# sch_CPU.net
KiCad netlist of a schematic drawn in Altium Designer
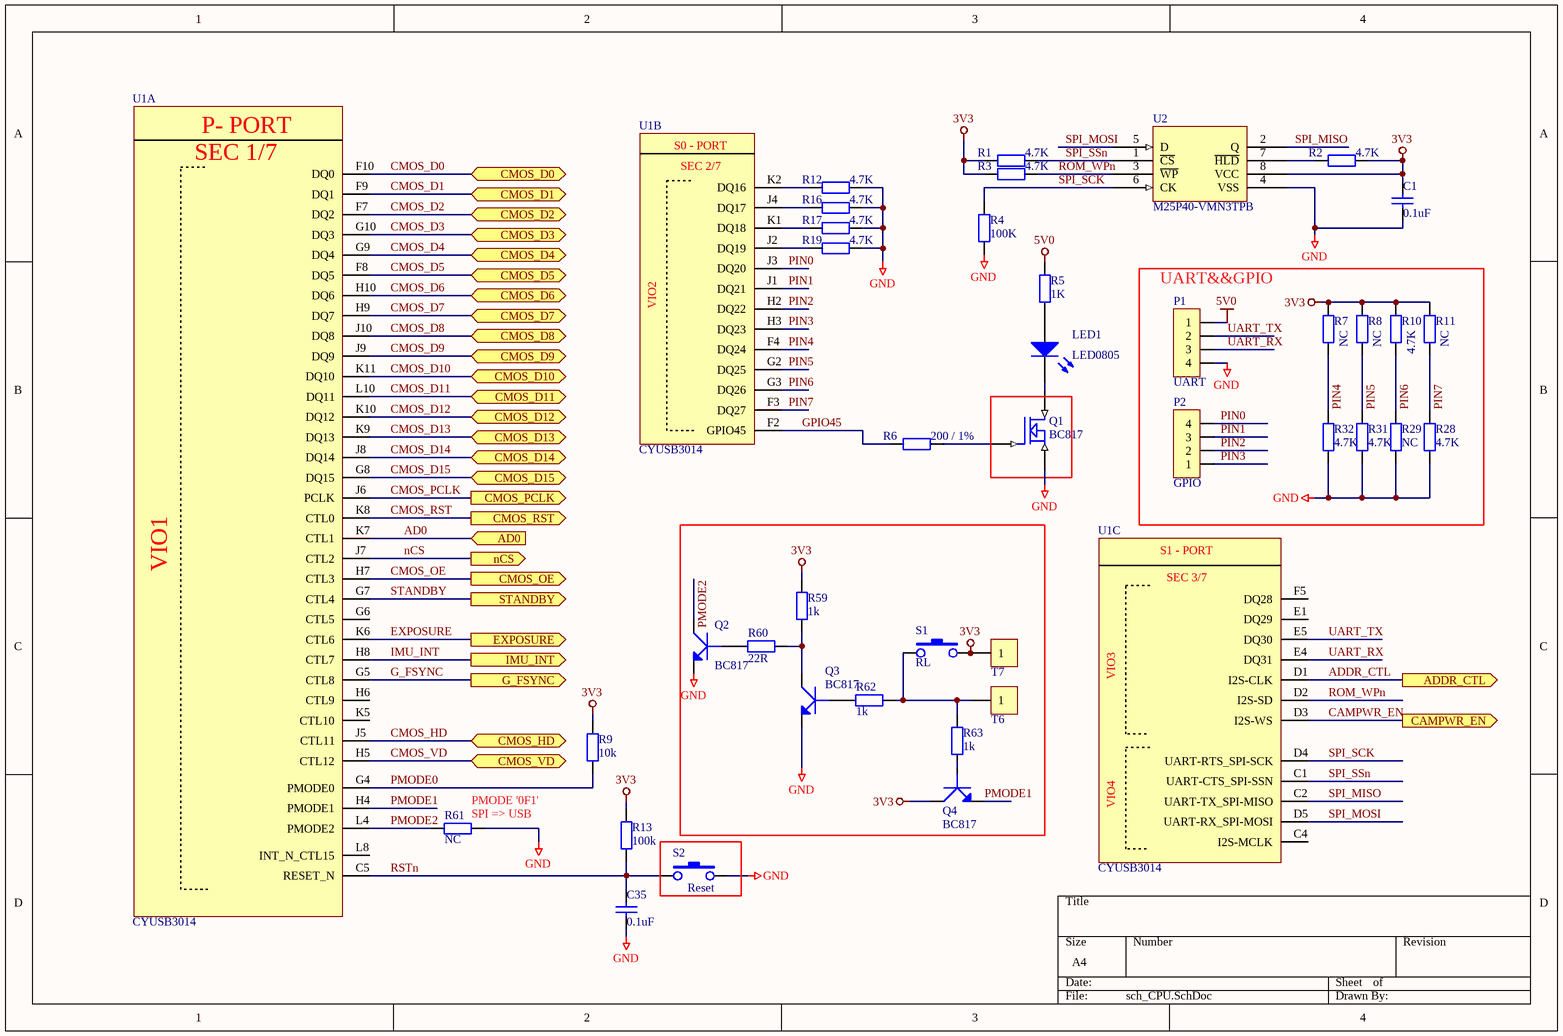
[diagram p0: sch_CPU.SchDoc]

(export (version "E")
  (design (tool "Eeschema 10.0.6"))
  (components
    (comp (ref "C1")
      (value "0.1uF")
      (footprint "0402C")
      (description "Capacitor")
      (fields (field (name "PUBLISHER") "Altium Limited"))
      (libsource (lib "Miscellaneous Devices") (part "Cap"))
    )
    (comp (ref "C35")
      (value "0.1uF")
      (footprint "0402C")
      (description "Capacitor")
      (fields (field (name "PUBLISHER") "Altium Limited"))
      (libsource (lib "Miscellaneous Devices") (part "Cap"))
    )
    (comp (ref "LED1")
      (value "LED0805")
      (footprint "LED0805A_L210W100H60")
      (description "发光二级管")
      (libsource (lib "TXW") (part "LED"))
    )
    (comp (ref "P1")
      (value "UART")
      (footprint "WAFER4_P1.25L6.25W3.4H4.3")
      (libsource (lib "KS_Drive") (part "CON4"))
    )
    (comp (ref "P2")
      (value "GPIO")
      (footprint "WAFER4_P1.25L6.25W3.4H4.3")
      (libsource (lib "") (part "CON4_1"))
    )
    (comp (ref "Q1")
      (value "BC817")
      (footprint "SOT-23L")
      (description "MOSFET N")
      (libsource (lib "TXW") (part "MOSFET N"))
    )
    (comp (ref "Q2")
      (value "BC817")
      (footprint "SOT-23L")
      (description "NPN Transistor")
      (libsource (lib "*") (part "NPN"))
    )
    (comp (ref "Q3")
      (value "BC817")
      (footprint "SOT-23L")
      (description "NPN Transistor")
      (libsource (lib "*") (part "NPN"))
    )
    (comp (ref "Q4")
      (value "BC817")
      (footprint "SOT-23L")
      (description "NPN Transistor")
      (libsource (lib "") (part "NPN_1"))
    )
    (comp (ref "R1")
      (value "4.7K")
      (footprint "0402R")
      (description "Resistor")
      (fields (field (name "PUBLISHER") "Altium Limited"))
      (libsource (lib "SZG") (part "Resistor"))
    )
    (comp (ref "R2")
      (value "4.7K")
      (footprint "0402R")
      (description "Resistor")
      (fields (field (name "PUBLISHER") "Altium Limited"))
      (libsource (lib "SZG") (part "Resistor"))
    )
    (comp (ref "R3")
      (value "4.7K")
      (footprint "0402R")
      (description "Resistor")
      (fields (field (name "PUBLISHER") "Altium Limited"))
      (libsource (lib "SZG") (part "Resistor"))
    )
    (comp (ref "R4")
      (value "100K")
      (footprint "0402R")
      (description "Resistor")
      (fields (field (name "PUBLISHER") "Altium Limited"))
      (libsource (lib "") (part "Resistor_1"))
    )
    (comp (ref "R5")
      (value "1K")
      (footprint "0402R")
      (description "Resistor")
      (fields (field (name "PUBLISHER") "Altium Limited"))
      (libsource (lib "") (part "Resistor_2"))
    )
    (comp (ref "R6")
      (value "200 / 1%")
      (footprint "0402R")
      (description "Resistor")
      (fields (field (name "Comment") "200R") (field (name "PUBLISHER") "Altium Limited"))
      (libsource (lib "SZG") (part "Resistor"))
    )
    (comp (ref "R7")
      (value "NC")
      (footprint "0402R")
      (description "Resistor")
      (fields (field (name "PUBLISHER") "Altium Limited"))
      (libsource (lib "") (part "Resistor_1"))
    )
    (comp (ref "R8")
      (value "NC")
      (footprint "0402R")
      (description "Resistor")
      (fields (field (name "PUBLISHER") "Altium Limited"))
      (libsource (lib "") (part "Resistor_1"))
    )
    (comp (ref "R9")
      (value "10k")
      (footprint "0402R")
      (description "Resistor")
      (fields (field (name "Comment") "10K") (field (name "PUBLISHER") "Altium Limited"))
      (libsource (lib "") (part "Resistor_2"))
    )
    (comp (ref "R10")
      (value "4.7K")
      (footprint "0402R")
      (description "Resistor")
      (fields (field (name "PUBLISHER") "Altium Limited"))
      (libsource (lib "") (part "Resistor_1"))
    )
    (comp (ref "R11")
      (value "NC")
      (footprint "0402R")
      (description "Resistor")
      (fields (field (name "PUBLISHER") "Altium Limited"))
      (libsource (lib "") (part "Resistor_1"))
    )
    (comp (ref "R12")
      (value "4.7K")
      (footprint "0402R")
      (description "Resistor")
      (fields (field (name "PUBLISHER") "Altium Limited"))
      (libsource (lib "SZG") (part "Resistor"))
    )
    (comp (ref "R13")
      (value "100k")
      (footprint "0402R")
      (description "Resistor")
      (fields (field (name "Comment") "100K") (field (name "PUBLISHER") "Altium Limited"))
      (libsource (lib "") (part "Resistor_2"))
    )
    (comp (ref "R16")
      (value "4.7K")
      (footprint "0402R")
      (description "Resistor")
      (fields (field (name "PUBLISHER") "Altium Limited"))
      (libsource (lib "SZG") (part "Resistor"))
    )
    (comp (ref "R17")
      (value "4.7K")
      (footprint "0402R")
      (description "Resistor")
      (fields (field (name "PUBLISHER") "Altium Limited"))
      (libsource (lib "SZG") (part "Resistor"))
    )
    (comp (ref "R19")
      (value "4.7K")
      (footprint "0402R")
      (description "Resistor")
      (fields (field (name "PUBLISHER") "Altium Limited"))
      (libsource (lib "SZG") (part "Resistor"))
    )
    (comp (ref "R28")
      (value "4.7K")
      (footprint "0402R")
      (description "Resistor")
      (fields (field (name "PUBLISHER") "Altium Limited"))
      (libsource (lib "") (part "Resistor_2"))
    )
    (comp (ref "R29")
      (value "NC")
      (footprint "0402R")
      (description "Resistor")
      (fields (field (name "PUBLISHER") "Altium Limited"))
      (libsource (lib "") (part "Resistor_2"))
    )
    (comp (ref "R31")
      (value "4.7K")
      (footprint "0402R")
      (description "Resistor")
      (fields (field (name "PUBLISHER") "Altium Limited"))
      (libsource (lib "") (part "Resistor_2"))
    )
    (comp (ref "R32")
      (value "4.7K")
      (footprint "0402R")
      (description "Resistor")
      (fields (field (name "PUBLISHER") "Altium Limited"))
      (libsource (lib "") (part "Resistor_2"))
    )
    (comp (ref "R59")
      (value "1k")
      (footprint "0402R")
      (description "Resistor")
      (fields (field (name "Comment") "1K") (field (name "PUBLISHER") "Altium Limited"))
      (libsource (lib "") (part "Resistor_1"))
    )
    (comp (ref "R60")
      (value "22R")
      (footprint "0402R")
      (description "Resistor")
      (fields (field (name "PUBLISHER") "Altium Limited"))
      (libsource (lib "SZG") (part "Resistor"))
    )
    (comp (ref "R61")
      (value "NC")
      (footprint "0805R")
      (description "Resistor")
      (fields (field (name "PUBLISHER") "Altium Limited"))
      (libsource (lib "") (part "Resistor_3"))
    )
    (comp (ref "R62")
      (value "1k")
      (footprint "0402R")
      (description "Resistor")
      (fields (field (name "PUBLISHER") "Altium Limited"))
      (libsource (lib "") (part "Resistor_3"))
    )
    (comp (ref "R63")
      (value "1k")
      (footprint "0402R")
      (description "Resistor")
      (fields (field (name "PUBLISHER") "Altium Limited"))
      (libsource (lib "") (part "Resistor_2"))
    )
    (comp (ref "S1")
      (value "RL")
      (footprint "SW_L40W30H25_MPTFP")
      (description "Button_sop")
      (libsource (lib "SZG") (part "Button_sop"))
    )
    (comp (ref "S2")
      (value "Reset")
      (footprint "SW_L40W30H25_MPTFP")
      (description "Button_sop")
      (libsource (lib "SZG") (part "Button_sop"))
    )
    (comp (ref "T6")
      (value "CON1")
      (footprint "PAD_TP_D1.2")
      (description "Connector")
      (libsource (lib "SuperSchLib") (part "CON1"))
    )
    (comp (ref "T7")
      (value "CON1")
      (footprint "PAD_TP_D1.2")
      (description "Connector")
      (libsource (lib "SuperSchLib") (part "CON1"))
    )
    (comp (ref "U1")
      (value "CYUSB3014")
      (footprint "FBGA121_P80L100W100H11")
      (libsource (lib "TXW") (part "CYUSB3014"))
    )
    (comp (ref "U2")
      (value "M25P40-VMN3TPB")
      (footprint "SO8N_P127L50W40W62H17")
      (libsource (lib "TXW") (part "M25P40-VMN3TPB"))
    )
  )
  (nets
    (net (code "1") (name "/AD0") (class "Default")
      (node (ref "U1") (pin "K7") (pinfunction "CTL1_K7") (pintype "passive"))
    )
    (net (code "2") (name "/ADDR_CTL") (class "Default")
      (node (ref "U1") (pin "D1") (pinfunction "I2S-CLK_D1") (pintype "passive"))
    )
    (net (code "3") (name "/CAMPWR_EN") (class "Default")
      (node (ref "U1") (pin "D3") (pinfunction "I2S-WS_D3") (pintype "passive"))
    )
    (net (code "4") (name "/CMOS_D0") (class "Default")
      (node (ref "U1") (pin "F10") (pinfunction "DQ0_F10") (pintype "passive"))
    )
    (net (code "5") (name "/CMOS_D1") (class "Default")
      (node (ref "U1") (pin "F9") (pinfunction "DQ1_F9") (pintype "passive"))
    )
    (net (code "6") (name "/CMOS_D2") (class "Default")
      (node (ref "U1") (pin "F7") (pinfunction "DQ2_F7") (pintype "passive"))
    )
    (net (code "7") (name "/CMOS_D3") (class "Default")
      (node (ref "U1") (pin "G10") (pinfunction "DQ3_G10") (pintype "passive"))
    )
    (net (code "8") (name "/CMOS_D4") (class "Default")
      (node (ref "U1") (pin "G9") (pinfunction "DQ4_G9") (pintype "passive"))
    )
    (net (code "9") (name "/CMOS_D5") (class "Default")
      (node (ref "U1") (pin "F8") (pinfunction "DQ5_F8") (pintype "passive"))
    )
    (net (code "10") (name "/CMOS_D6") (class "Default")
      (node (ref "U1") (pin "H10") (pinfunction "DQ6_H10") (pintype "passive"))
    )
    (net (code "11") (name "/CMOS_D7") (class "Default")
      (node (ref "U1") (pin "H9") (pinfunction "DQ7_H9") (pintype "passive"))
    )
    (net (code "12") (name "/CMOS_D8") (class "Default")
      (node (ref "U1") (pin "J10") (pinfunction "DQ8_J10") (pintype "passive"))
    )
    (net (code "13") (name "/CMOS_D9") (class "Default")
      (node (ref "U1") (pin "J9") (pinfunction "DQ9_J9") (pintype "passive"))
    )
    (net (code "14") (name "/CMOS_D10") (class "Default")
      (node (ref "U1") (pin "K11") (pinfunction "DQ10_K11") (pintype "passive"))
    )
    (net (code "15") (name "/CMOS_D11") (class "Default")
      (node (ref "U1") (pin "L10") (pinfunction "DQ11_L10") (pintype "passive"))
    )
    (net (code "16") (name "/CMOS_D12") (class "Default")
      (node (ref "U1") (pin "K10") (pinfunction "DQ12_K10") (pintype "passive"))
    )
    (net (code "17") (name "/CMOS_D13") (class "Default")
      (node (ref "U1") (pin "K9") (pinfunction "DQ13_K9") (pintype "passive"))
    )
    (net (code "18") (name "/CMOS_D14") (class "Default")
      (node (ref "U1") (pin "J8") (pinfunction "DQ14_J8") (pintype "passive"))
    )
    (net (code "19") (name "/CMOS_D15") (class "Default")
      (node (ref "U1") (pin "G8") (pinfunction "DQ15_G8") (pintype "passive"))
    )
    (net (code "20") (name "/CMOS_HD") (class "Default")
      (node (ref "U1") (pin "J5") (pinfunction "CTL11_J5") (pintype "passive"))
    )
    (net (code "21") (name "/CMOS_OE") (class "Default")
      (node (ref "U1") (pin "H7") (pinfunction "CTL3_H7") (pintype "passive"))
    )
    (net (code "22") (name "/CMOS_PCLK") (class "Default")
      (node (ref "U1") (pin "J6") (pinfunction "PCLK_J6") (pintype "passive"))
    )
    (net (code "23") (name "/CMOS_RST") (class "Default")
      (node (ref "U1") (pin "K8") (pinfunction "CTL0_K8") (pintype "passive"))
    )
    (net (code "24") (name "/CMOS_VD") (class "Default")
      (node (ref "U1") (pin "H5") (pinfunction "CTL12_H5") (pintype "passive"))
    )
    (net (code "25") (name "/EXPOSURE") (class "Default")
      (node (ref "U1") (pin "K6") (pinfunction "CTL6_K6") (pintype "passive"))
    )
    (net (code "26") (name "/GPIO45") (class "Default")
      (node (ref "R6") (pin "1") (pinfunction "1_1") (pintype "passive"))
      (node (ref "U1") (pin "F2") (pinfunction "GPIO45_F2") (pintype "passive"))
    )
    (net (code "27") (name "/G_FSYNC") (class "Default")
      (node (ref "U1") (pin "G5") (pinfunction "CTL8_G5") (pintype "passive"))
    )
    (net (code "28") (name "/IMU_INT") (class "Default")
      (node (ref "U1") (pin "H8") (pinfunction "CTL7_H8") (pintype "passive"))
    )
    (net (code "29") (name "/PIN0") (class "Default")
      (node (ref "P2") (pin "4") (pinfunction "4_4") (pintype "passive"))
      (node (ref "U1") (pin "J3") (pinfunction "DQ20_J3") (pintype "passive"))
    )
    (net (code "30") (name "/PIN1") (class "Default")
      (node (ref "P2") (pin "3") (pinfunction "3_3") (pintype "passive"))
      (node (ref "U1") (pin "J1") (pinfunction "DQ21_J1") (pintype "passive"))
    )
    (net (code "31") (name "/PIN2") (class "Default")
      (node (ref "P2") (pin "2") (pinfunction "2_2") (pintype "passive"))
      (node (ref "U1") (pin "H2") (pinfunction "DQ22_H2") (pintype "passive"))
    )
    (net (code "32") (name "/PIN3") (class "Default")
      (node (ref "P2") (pin "1") (pinfunction "1_1") (pintype "passive"))
      (node (ref "U1") (pin "H3") (pinfunction "DQ23_H3") (pintype "passive"))
    )
    (net (code "33") (name "/PIN4") (class "Default")
      (node (ref "R32") (pin "1") (pinfunction "1_1") (pintype "passive"))
      (node (ref "R7") (pin "1") (pinfunction "1_1") (pintype "passive"))
      (node (ref "U1") (pin "F4") (pinfunction "DQ24_F4") (pintype "passive"))
    )
    (net (code "34") (name "/PIN5") (class "Default")
      (node (ref "R31") (pin "1") (pinfunction "1_1") (pintype "passive"))
      (node (ref "R8") (pin "1") (pinfunction "1_1") (pintype "passive"))
      (node (ref "U1") (pin "G2") (pinfunction "DQ25_G2") (pintype "passive"))
    )
    (net (code "35") (name "/PIN6") (class "Default")
      (node (ref "R10") (pin "1") (pinfunction "1_1") (pintype "passive"))
      (node (ref "R29") (pin "1") (pinfunction "1_1") (pintype "passive"))
      (node (ref "U1") (pin "G3") (pinfunction "DQ26_G3") (pintype "passive"))
    )
    (net (code "36") (name "/PIN7") (class "Default")
      (node (ref "R11") (pin "1") (pinfunction "1_1") (pintype "passive"))
      (node (ref "R28") (pin "1") (pinfunction "1_1") (pintype "passive"))
      (node (ref "U1") (pin "F3") (pinfunction "DQ27_F3") (pintype "passive"))
    )
    (net (code "37") (name "/PMODE0") (class "Default")
      (node (ref "R9") (pin "2") (pinfunction "2_2") (pintype "passive"))
      (node (ref "U1") (pin "G4") (pinfunction "PMODE0_G4") (pintype "passive"))
    )
    (net (code "38") (name "/PMODE1") (class "Default")
      (node (ref "Q4") (pin "2") (pinfunction "E_2") (pintype "passive"))
      (node (ref "U1") (pin "H4") (pinfunction "PMODE1_H4") (pintype "passive"))
    )
    (net (code "39") (name "/PMODE2") (class "Default")
      (node (ref "Q2") (pin "3") (pinfunction "C_3") (pintype "passive"))
      (node (ref "R61") (pin "2") (pinfunction "2_2") (pintype "passive"))
      (node (ref "U1") (pin "L4") (pinfunction "PMODE2_L4") (pintype "passive"))
    )
    (net (code "40") (name "/ROM_WPn") (class "Default")
      (node (ref "R3") (pin "2") (pinfunction "2_2") (pintype "passive"))
      (node (ref "U1") (pin "D2") (pinfunction "I2S-SD_D2") (pintype "passive"))
      (node (ref "U2") (pin "3") (pinfunction "~{WP}_3") (pintype "passive"))
    )
    (net (code "41") (name "/RSTn") (class "Default")
      (node (ref "C35") (pin "2") (pinfunction "2_2") (pintype "passive"))
      (node (ref "R13") (pin "2") (pinfunction "2_2") (pintype "passive"))
      (node (ref "S2") (pin "1") (pinfunction "1_1") (pintype "passive"))
      (node (ref "U1") (pin "C5") (pinfunction "RESET_N_C5") (pintype "passive"))
    )
    (net (code "42") (name "/SPI_MISO") (class "Default")
      (node (ref "U1") (pin "C2") (pinfunction "UART-TX_SPI-MISO_C2") (pintype "passive"))
      (node (ref "U2") (pin "2") (pinfunction "Q_2") (pintype "passive"))
    )
    (net (code "43") (name "/SPI_MOSI") (class "Default")
      (node (ref "U1") (pin "D5") (pinfunction "UART-RX_SPI-MOSI_D5") (pintype "passive"))
      (node (ref "U2") (pin "5") (pinfunction "D_5") (pintype "input"))
    )
    (net (code "44") (name "/SPI_SCK") (class "Default")
      (node (ref "R4") (pin "2") (pinfunction "2_2") (pintype "passive"))
      (node (ref "U1") (pin "D4") (pinfunction "UART-RTS_SPI-SCK_D4") (pintype "passive"))
      (node (ref "U2") (pin "6") (pinfunction "CK_6") (pintype "input"))
    )
    (net (code "45") (name "/SPI_SSn") (class "Default")
      (node (ref "R1") (pin "2") (pinfunction "2_2") (pintype "passive"))
      (node (ref "U1") (pin "C1") (pinfunction "UART-CTS_SPI-SSN_C1") (pintype "passive"))
      (node (ref "U2") (pin "1") (pinfunction "~{CS}_1") (pintype "passive"))
    )
    (net (code "46") (name "/STANDBY") (class "Default")
      (node (ref "U1") (pin "G7") (pinfunction "CTL4_G7") (pintype "passive"))
    )
    (net (code "47") (name "/UART_RX") (class "Default")
      (node (ref "P1") (pin "3") (pinfunction "3_3") (pintype "passive"))
      (node (ref "U1") (pin "E4") (pinfunction "DQ31_E4") (pintype "passive"))
    )
    (net (code "48") (name "/UART_TX") (class "Default")
      (node (ref "P1") (pin "2") (pinfunction "2_2") (pintype "passive"))
      (node (ref "U1") (pin "E5") (pinfunction "DQ30_E5") (pintype "passive"))
    )
    (net (code "49") (name "/nCS") (class "Default")
      (node (ref "U1") (pin "J7") (pinfunction "CTL2_J7") (pintype "passive"))
    )
    (net (code "50") (name "3V3") (class "Default")
      (node (ref "C1") (pin "2") (pinfunction "2_2") (pintype "passive"))
      (node (ref "Q4") (pin "3") (pinfunction "C_3") (pintype "passive"))
      (node (ref "R1") (pin "1") (pinfunction "1_1") (pintype "passive"))
      (node (ref "R10") (pin "2") (pinfunction "2_2") (pintype "passive"))
      (node (ref "R11") (pin "2") (pinfunction "2_2") (pintype "passive"))
      (node (ref "R13") (pin "1") (pinfunction "1_1") (pintype "passive"))
      (node (ref "R2") (pin "2") (pinfunction "2_2") (pintype "passive"))
      (node (ref "R3") (pin "1") (pinfunction "1_1") (pintype "passive"))
      (node (ref "R59") (pin "2") (pinfunction "2_2") (pintype "passive"))
      (node (ref "R7") (pin "2") (pinfunction "2_2") (pintype "passive"))
      (node (ref "R8") (pin "2") (pinfunction "2_2") (pintype "passive"))
      (node (ref "R9") (pin "1") (pinfunction "1_1") (pintype "passive"))
      (node (ref "S1") (pin "1") (pinfunction "1_1") (pintype "passive"))
      (node (ref "T7") (pin "1") (pinfunction "1_1") (pintype "passive"))
      (node (ref "U2") (pin "8") (pinfunction "VCC_8") (pintype "passive"))
    )
    (net (code "51") (name "5V0") (class "Default")
      (node (ref "P1") (pin "1") (pinfunction "1_1") (pintype "passive"))
      (node (ref "R5") (pin "1") (pinfunction "1_1") (pintype "passive"))
    )
    (net (code "52") (name "GND") (class "Default")
      (node (ref "C1") (pin "1") (pinfunction "1_1") (pintype "passive"))
      (node (ref "C35") (pin "1") (pinfunction "1_1") (pintype "passive"))
      (node (ref "P1") (pin "4") (pinfunction "4_4") (pintype "passive"))
      (node (ref "Q1") (pin "2") (pinfunction "S_2") (pintype "input"))
      (node (ref "Q2") (pin "2") (pinfunction "E_2") (pintype "passive"))
      (node (ref "Q3") (pin "2") (pinfunction "E_2") (pintype "passive"))
      (node (ref "R12") (pin "2") (pinfunction "2_2") (pintype "passive"))
      (node (ref "R16") (pin "2") (pinfunction "2_2") (pintype "passive"))
      (node (ref "R17") (pin "2") (pinfunction "2_2") (pintype "passive"))
      (node (ref "R19") (pin "2") (pinfunction "2_2") (pintype "passive"))
      (node (ref "R28") (pin "2") (pinfunction "2_2") (pintype "passive"))
      (node (ref "R29") (pin "2") (pinfunction "2_2") (pintype "passive"))
      (node (ref "R31") (pin "2") (pinfunction "2_2") (pintype "passive"))
      (node (ref "R32") (pin "2") (pinfunction "2_2") (pintype "passive"))
      (node (ref "R4") (pin "1") (pinfunction "1_1") (pintype "passive"))
      (node (ref "R61") (pin "1") (pinfunction "1_1") (pintype "passive"))
      (node (ref "S2") (pin "2") (pinfunction "2_2") (pintype "passive"))
      (node (ref "U2") (pin "4") (pinfunction "VSS_4") (pintype "passive"))
    )
    (net (code "53") (name "Net-(LED1-A)") (class "Default")
      (node (ref "LED1") (pin "1") (pinfunction "A_1") (pintype "passive"))
      (node (ref "R5") (pin "2") (pinfunction "2_2") (pintype "passive"))
    )
    (net (code "54") (name "Net-(LED1-K)") (class "Default")
      (node (ref "LED1") (pin "2") (pinfunction "K_2") (pintype "passive"))
      (node (ref "Q1") (pin "3") (pinfunction "D_3") (pintype "input"))
    )
    (net (code "55") (name "Net-(Q1-G)") (class "Default")
      (node (ref "Q1") (pin "1") (pinfunction "G_1") (pintype "input"))
      (node (ref "R6") (pin "2") (pinfunction "2_2") (pintype "passive"))
    )
    (net (code "56") (name "Net-(Q2-B)") (class "Default")
      (node (ref "Q2") (pin "1") (pinfunction "B_1") (pintype "passive"))
      (node (ref "R60") (pin "1") (pinfunction "1_1") (pintype "passive"))
    )
    (net (code "57") (name "Net-(Q3-B)") (class "Default")
      (node (ref "Q3") (pin "1") (pinfunction "B_1") (pintype "passive"))
      (node (ref "R62") (pin "2") (pinfunction "2_2") (pintype "passive"))
    )
    (net (code "58") (name "Net-(Q3-C)") (class "Default")
      (node (ref "Q3") (pin "3") (pinfunction "C_3") (pintype "passive"))
      (node (ref "R59") (pin "1") (pinfunction "1_1") (pintype "passive"))
      (node (ref "R60") (pin "2") (pinfunction "2_2") (pintype "passive"))
    )
    (net (code "59") (name "Net-(Q4-B)") (class "Default")
      (node (ref "Q4") (pin "1") (pinfunction "B_1") (pintype "passive"))
      (node (ref "R63") (pin "2") (pinfunction "2_2") (pintype "passive"))
    )
    (net (code "60") (name "Net-(R62-Pad1)") (class "Default")
      (node (ref "R62") (pin "1") (pinfunction "1_1") (pintype "passive"))
      (node (ref "R63") (pin "1") (pinfunction "1_1") (pintype "passive"))
      (node (ref "S1") (pin "2") (pinfunction "2_2") (pintype "passive"))
      (node (ref "T6") (pin "1") (pinfunction "1_1") (pintype "passive"))
    )
    (net (code "61") (name "Net-(U1B-DQ16)") (class "Default")
      (node (ref "R12") (pin "1") (pinfunction "1_1") (pintype "passive"))
      (node (ref "U1") (pin "K2") (pinfunction "DQ16_K2") (pintype "passive"))
    )
    (net (code "62") (name "Net-(U1B-DQ17)") (class "Default")
      (node (ref "R16") (pin "1") (pinfunction "1_1") (pintype "passive"))
      (node (ref "U1") (pin "J4") (pinfunction "DQ17_J4") (pintype "passive"))
    )
    (net (code "63") (name "Net-(U1B-DQ18)") (class "Default")
      (node (ref "R17") (pin "1") (pinfunction "1_1") (pintype "passive"))
      (node (ref "U1") (pin "K1") (pinfunction "DQ18_K1") (pintype "passive"))
    )
    (net (code "64") (name "Net-(U1B-DQ19)") (class "Default")
      (node (ref "R19") (pin "1") (pinfunction "1_1") (pintype "passive"))
      (node (ref "U1") (pin "J2") (pinfunction "DQ19_J2") (pintype "passive"))
    )
    (net (code "65") (name "Net-(U2-~{HLD})") (class "Default")
      (node (ref "R2") (pin "1") (pinfunction "1_1") (pintype "passive"))
      (node (ref "U2") (pin "7") (pinfunction "~{HLD}_7") (pintype "passive"))
    )
    (net (code "66") (name "unconnected-(U1A-CTL5-PadG6)") (class "Default")
      (node (ref "U1") (pin "G6") (pinfunction "CTL5_G6") (pintype "passive"))
    )
    (net (code "67") (name "unconnected-(U1A-CTL9-PadH6)") (class "Default")
      (node (ref "U1") (pin "H6") (pinfunction "CTL9_H6") (pintype "passive"))
    )
    (net (code "68") (name "unconnected-(U1A-CTL10-PadK5)") (class "Default")
      (node (ref "U1") (pin "K5") (pinfunction "CTL10_K5") (pintype "passive"))
    )
    (net (code "69") (name "unconnected-(U1A-INT_N_CTL15-PadL8)") (class "Default")
      (node (ref "U1") (pin "L8") (pinfunction "INT_N_CTL15_L8") (pintype "passive"))
    )
    (net (code "70") (name "unconnected-(U1C-DQ28-PadF5)") (class "Default")
      (node (ref "U1") (pin "F5") (pinfunction "DQ28_F5") (pintype "passive"))
    )
    (net (code "71") (name "unconnected-(U1C-DQ29-PadE1)") (class "Default")
      (node (ref "U1") (pin "E1") (pinfunction "DQ29_E1") (pintype "passive"))
    )
    (net (code "72") (name "unconnected-(U1C-I2S-MCLK-PadC4)") (class "Default")
      (node (ref "U1") (pin "C4") (pinfunction "I2S-MCLK_C4") (pintype "passive"))
    )
  )
)
